# Ad8232_placa_V5.net
KiCad netlist of a schematic drawn in EAGLE
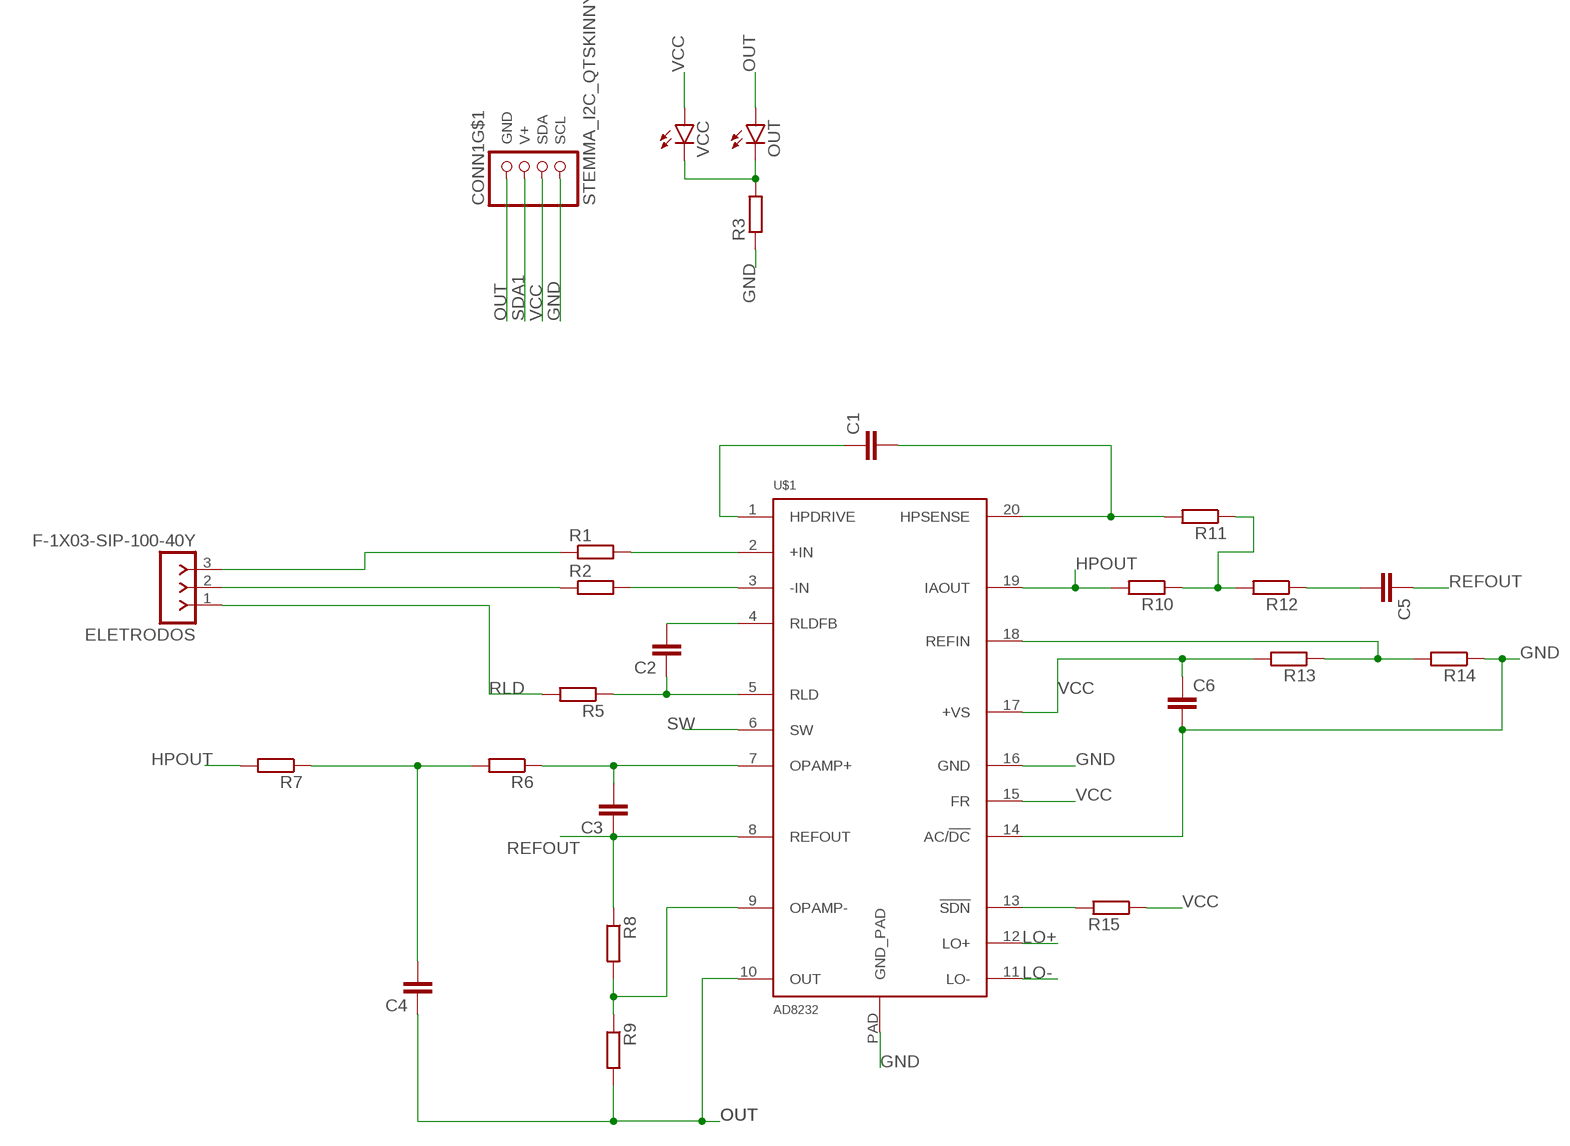
[diagram p0: schematic, sheet 1]

(export (version "E")
  (design (tool "Eeschema 10.0.6"))
  (components
    (comp (ref "C1")
      (value "C-EUC0402K")
      (footprint "eagle-import:C0402K")
      (libsource (lib "eagle-import") (part "C-EUC0402K"))
    )
    (comp (ref "C2")
      (value "C-EUC0402K")
      (footprint "eagle-import:C0402K")
      (libsource (lib "eagle-import") (part "C-EUC0402K"))
    )
    (comp (ref "C3")
      (value "C-EUC0402K")
      (footprint "eagle-import:C0402K")
      (libsource (lib "eagle-import") (part "C-EUC0402K"))
    )
    (comp (ref "C4")
      (value "C-EUC0402K")
      (footprint "eagle-import:C0402K")
      (libsource (lib "eagle-import") (part "C-EUC0402K"))
    )
    (comp (ref "C5")
      (value "C-EUC0402K")
      (footprint "eagle-import:C0402K")
      (libsource (lib "eagle-import") (part "C-EUC0402K"))
    )
    (comp (ref "C6")
      (value "C-EUC0402K")
      (footprint "eagle-import:C0402K")
      (libsource (lib "eagle-import") (part "C-EUC0402K"))
    )
    (comp (ref "CONN1")
      (value "STEMMA_I2C_QTSKINNY")
      (footprint "eagle-import:JST_SH4_SKINNY")
      (libsource (lib "eagle-import") (part "STEMMA_I2C_QTSKINNY"))
    )
    (comp (ref "ELETRODOS")
      (value "F-1X03-SIP-100-40Y")
      (footprint "eagle-import:SIP-100-03-40Y")
      (libsource (lib "eagle-import") (part "F-1X03-SIP-100-40Y"))
    )
    (comp (ref "OUT")
      (value "LEDCHIPLED_0603")
      (footprint "eagle-import:CHIPLED_0603")
      (libsource (lib "eagle-import") (part "LEDCHIPLED_0603"))
    )
    (comp (ref "R1")
      (value "R-EU_R0402")
      (footprint "eagle-import:R0402")
      (libsource (lib "eagle-import") (part "R-EU_R0402"))
    )
    (comp (ref "R2")
      (value "R-EU_R0402")
      (footprint "eagle-import:R0402")
      (libsource (lib "eagle-import") (part "R-EU_R0402"))
    )
    (comp (ref "R3")
      (value "R-EU_R0402")
      (footprint "eagle-import:R0402")
      (libsource (lib "eagle-import") (part "R-EU_R0402"))
    )
    (comp (ref "R5")
      (value "R-EU_R0402")
      (footprint "eagle-import:R0402")
      (libsource (lib "eagle-import") (part "R-EU_R0402"))
    )
    (comp (ref "R6")
      (value "R-EU_R0402")
      (footprint "eagle-import:R0402")
      (libsource (lib "eagle-import") (part "R-EU_R0402"))
    )
    (comp (ref "R7")
      (value "R-EU_R0402")
      (footprint "eagle-import:R0402")
      (libsource (lib "eagle-import") (part "R-EU_R0402"))
    )
    (comp (ref "R8")
      (value "R-EU_R0402")
      (footprint "eagle-import:R0402")
      (libsource (lib "eagle-import") (part "R-EU_R0402"))
    )
    (comp (ref "R9")
      (value "R-EU_R0402")
      (footprint "eagle-import:R0402")
      (libsource (lib "eagle-import") (part "R-EU_R0402"))
    )
    (comp (ref "R10")
      (value "R-EU_R0402")
      (footprint "eagle-import:R0402")
      (libsource (lib "eagle-import") (part "R-EU_R0402"))
    )
    (comp (ref "R11")
      (value "R-EU_R0402")
      (footprint "eagle-import:R0402")
      (libsource (lib "eagle-import") (part "R-EU_R0402"))
    )
    (comp (ref "R12")
      (value "R-EU_R0402")
      (footprint "eagle-import:R0402")
      (libsource (lib "eagle-import") (part "R-EU_R0402"))
    )
    (comp (ref "R13")
      (value "R-EU_R0402")
      (footprint "eagle-import:R0402")
      (libsource (lib "eagle-import") (part "R-EU_R0402"))
    )
    (comp (ref "R14")
      (value "R-EU_R0402")
      (footprint "eagle-import:R0402")
      (libsource (lib "eagle-import") (part "R-EU_R0402"))
    )
    (comp (ref "R15")
      (value "R-EU_R0402")
      (footprint "eagle-import:R0402")
      (libsource (lib "eagle-import") (part "R-EU_R0402"))
    )
    (comp (ref "U$1")
      (value "AD8232")
      (footprint "eagle-import:LFCSP_20")
      (fields (field (name "MF") "Analog Devices"))
      (libsource (lib "eagle-import") (part "AD8232"))
    )
    (comp (ref "VCC")
      (value "LEDCHIPLED_0603")
      (footprint "eagle-import:CHIPLED_0603")
      (libsource (lib "eagle-import") (part "LEDCHIPLED_0603"))
    )
  )
  (nets
    (net (code "1") (name "/GND") (class "Default")
      (node (ref "C6") (pin "2") (pinfunction "2_2") (pintype "passive"))
      (node (ref "CONN1") (pin "4") (pinfunction "SCL_4") (pintype "passive"))
      (node (ref "R14") (pin "1") (pinfunction "1_1") (pintype "passive"))
      (node (ref "R3") (pin "1") (pinfunction "1_1") (pintype "passive"))
      (node (ref "U$1") (pin "14") (pinfunction "AC/~{DC}_14") (pintype "bidirectional"))
      (node (ref "U$1") (pin "16") (pinfunction "GND_16") (pintype "bidirectional"))
      (node (ref "U$1") (pin "PAD") (pinfunction "GND_PAD_PAD") (pintype "bidirectional"))
    )
    (net (code "2") (name "/HPOUT") (class "Default")
      (node (ref "R10") (pin "2") (pinfunction "2_2") (pintype "passive"))
      (node (ref "R7") (pin "2") (pinfunction "2_2") (pintype "passive"))
      (node (ref "U$1") (pin "19") (pinfunction "IAOUT_19") (pintype "bidirectional"))
    )
    (net (code "3") (name "/LO+") (class "Default")
      (node (ref "U$1") (pin "12") (pinfunction "LO+_12") (pintype "bidirectional"))
    )
    (net (code "4") (name "/LO-") (class "Default")
      (node (ref "U$1") (pin "11") (pinfunction "LO-_11") (pintype "bidirectional"))
    )
    (net (code "5") (name "/OUT") (class "Default")
      (node (ref "C4") (pin "1") (pinfunction "1_1") (pintype "passive"))
      (node (ref "CONN1") (pin "1") (pinfunction "GND_1") (pintype "passive"))
      (node (ref "OUT") (pin "A") (pinfunction "A_A") (pintype "passive"))
      (node (ref "R9") (pin "2") (pinfunction "2_2") (pintype "passive"))
      (node (ref "U$1") (pin "10") (pinfunction "OUT_10") (pintype "bidirectional"))
    )
    (net (code "6") (name "/REFOUT") (class "Default")
      (node (ref "C3") (pin "1") (pinfunction "1_1") (pintype "passive"))
      (node (ref "C5") (pin "1") (pinfunction "1_1") (pintype "passive"))
      (node (ref "R8") (pin "1") (pinfunction "1_1") (pintype "passive"))
      (node (ref "U$1") (pin "8") (pinfunction "REFOUT_8") (pintype "bidirectional"))
    )
    (net (code "7") (name "/RLD") (class "Default")
      (node (ref "ELETRODOS") (pin "1") (pinfunction "1_1") (pintype "passive"))
      (node (ref "R5") (pin "2") (pinfunction "2_2") (pintype "passive"))
    )
    (net (code "8") (name "/SDA1") (class "Default")
      (node (ref "CONN1") (pin "2") (pinfunction "V+_2") (pintype "passive"))
    )
    (net (code "9") (name "/SW") (class "Default")
      (node (ref "C5") (pin "2") (pinfunction "2_2") (pintype "passive"))
      (node (ref "R12") (pin "1") (pinfunction "1_1") (pintype "passive"))
      (node (ref "U$1") (pin "6") (pinfunction "SW_6") (pintype "bidirectional"))
    )
    (net (code "10") (name "/VCC") (class "Default")
      (node (ref "C6") (pin "1") (pinfunction "1_1") (pintype "passive"))
      (node (ref "CONN1") (pin "3") (pinfunction "SDA_3") (pintype "passive"))
      (node (ref "R13") (pin "2") (pinfunction "2_2") (pintype "passive"))
      (node (ref "R15") (pin "1") (pinfunction "1_1") (pintype "passive"))
      (node (ref "U$1") (pin "15") (pinfunction "FR_15") (pintype "bidirectional"))
      (node (ref "U$1") (pin "17") (pinfunction "+VS_17") (pintype "bidirectional"))
      (node (ref "VCC") (pin "A") (pinfunction "A_A") (pintype "passive"))
    )
    (net (code "11") (name "Net-(C4-Pad2)") (class "Default")
      (node (ref "C4") (pin "2") (pinfunction "2_2") (pintype "passive"))
      (node (ref "R6") (pin "2") (pinfunction "2_2") (pintype "passive"))
      (node (ref "R7") (pin "1") (pinfunction "1_1") (pintype "passive"))
    )
    (net (code "12") (name "Net-(ELETRODOS-Pad2)") (class "Default")
      (node (ref "ELETRODOS") (pin "2") (pinfunction "2_2") (pintype "passive"))
      (node (ref "R2") (pin "1") (pinfunction "1_1") (pintype "passive"))
    )
    (net (code "13") (name "Net-(ELETRODOS-Pad3)") (class "Default")
      (node (ref "ELETRODOS") (pin "3") (pinfunction "3_3") (pintype "passive"))
      (node (ref "R1") (pin "1") (pinfunction "1_1") (pintype "passive"))
    )
    (net (code "14") (name "Net-(OUT-PadC)") (class "Default")
      (node (ref "OUT") (pin "C") (pinfunction "C_C") (pintype "passive"))
      (node (ref "R3") (pin "2") (pinfunction "2_2") (pintype "passive"))
      (node (ref "VCC") (pin "C") (pinfunction "C_C") (pintype "passive"))
    )
    (net (code "15") (name "Net-(R10-Pad1)") (class "Default")
      (node (ref "R10") (pin "1") (pinfunction "1_1") (pintype "passive"))
      (node (ref "R11") (pin "1") (pinfunction "1_1") (pintype "passive"))
      (node (ref "R12") (pin "2") (pinfunction "2_2") (pintype "passive"))
    )
    (net (code "16") (name "Net-(U$1-+IN)") (class "Default")
      (node (ref "R1") (pin "2") (pinfunction "2_2") (pintype "passive"))
      (node (ref "U$1") (pin "2") (pinfunction "+IN_2") (pintype "bidirectional"))
    )
    (net (code "17") (name "Net-(U$1--IN)") (class "Default")
      (node (ref "R2") (pin "2") (pinfunction "2_2") (pintype "passive"))
      (node (ref "U$1") (pin "3") (pinfunction "-IN_3") (pintype "bidirectional"))
    )
    (net (code "18") (name "Net-(U$1-HPDRIVE)") (class "Default")
      (node (ref "C1") (pin "1") (pinfunction "1_1") (pintype "passive"))
      (node (ref "U$1") (pin "1") (pinfunction "HPDRIVE_1") (pintype "bidirectional"))
    )
    (net (code "19") (name "Net-(U$1-HPSENSE)") (class "Default")
      (node (ref "C1") (pin "2") (pinfunction "2_2") (pintype "passive"))
      (node (ref "R11") (pin "2") (pinfunction "2_2") (pintype "passive"))
      (node (ref "U$1") (pin "20") (pinfunction "HPSENSE_20") (pintype "bidirectional"))
    )
    (net (code "20") (name "Net-(U$1-OPAMP+)") (class "Default")
      (node (ref "C3") (pin "2") (pinfunction "2_2") (pintype "passive"))
      (node (ref "R6") (pin "1") (pinfunction "1_1") (pintype "passive"))
      (node (ref "U$1") (pin "7") (pinfunction "OPAMP+_7") (pintype "bidirectional"))
    )
    (net (code "21") (name "Net-(U$1-OPAMP-)") (class "Default")
      (node (ref "R8") (pin "2") (pinfunction "2_2") (pintype "passive"))
      (node (ref "R9") (pin "1") (pinfunction "1_1") (pintype "passive"))
      (node (ref "U$1") (pin "9") (pinfunction "OPAMP-_9") (pintype "bidirectional"))
    )
    (net (code "22") (name "Net-(U$1-REFIN)") (class "Default")
      (node (ref "R13") (pin "1") (pinfunction "1_1") (pintype "passive"))
      (node (ref "R14") (pin "2") (pinfunction "2_2") (pintype "passive"))
      (node (ref "U$1") (pin "18") (pinfunction "REFIN_18") (pintype "bidirectional"))
    )
    (net (code "23") (name "Net-(U$1-RLD)") (class "Default")
      (node (ref "C2") (pin "1") (pinfunction "1_1") (pintype "passive"))
      (node (ref "R5") (pin "1") (pinfunction "1_1") (pintype "passive"))
      (node (ref "U$1") (pin "5") (pinfunction "RLD_5") (pintype "bidirectional"))
    )
    (net (code "24") (name "Net-(U$1-RLDFB)") (class "Default")
      (node (ref "C2") (pin "2") (pinfunction "2_2") (pintype "passive"))
      (node (ref "U$1") (pin "4") (pinfunction "RLDFB_4") (pintype "bidirectional"))
    )
    (net (code "25") (name "Net-(U$1-~{SDN})") (class "Default")
      (node (ref "R15") (pin "2") (pinfunction "2_2") (pintype "passive"))
      (node (ref "U$1") (pin "13") (pinfunction "~{SDN}_13") (pintype "bidirectional"))
    )
  )
)
